# Power.net
KiCad netlist of a schematic drawn in Altium Designer
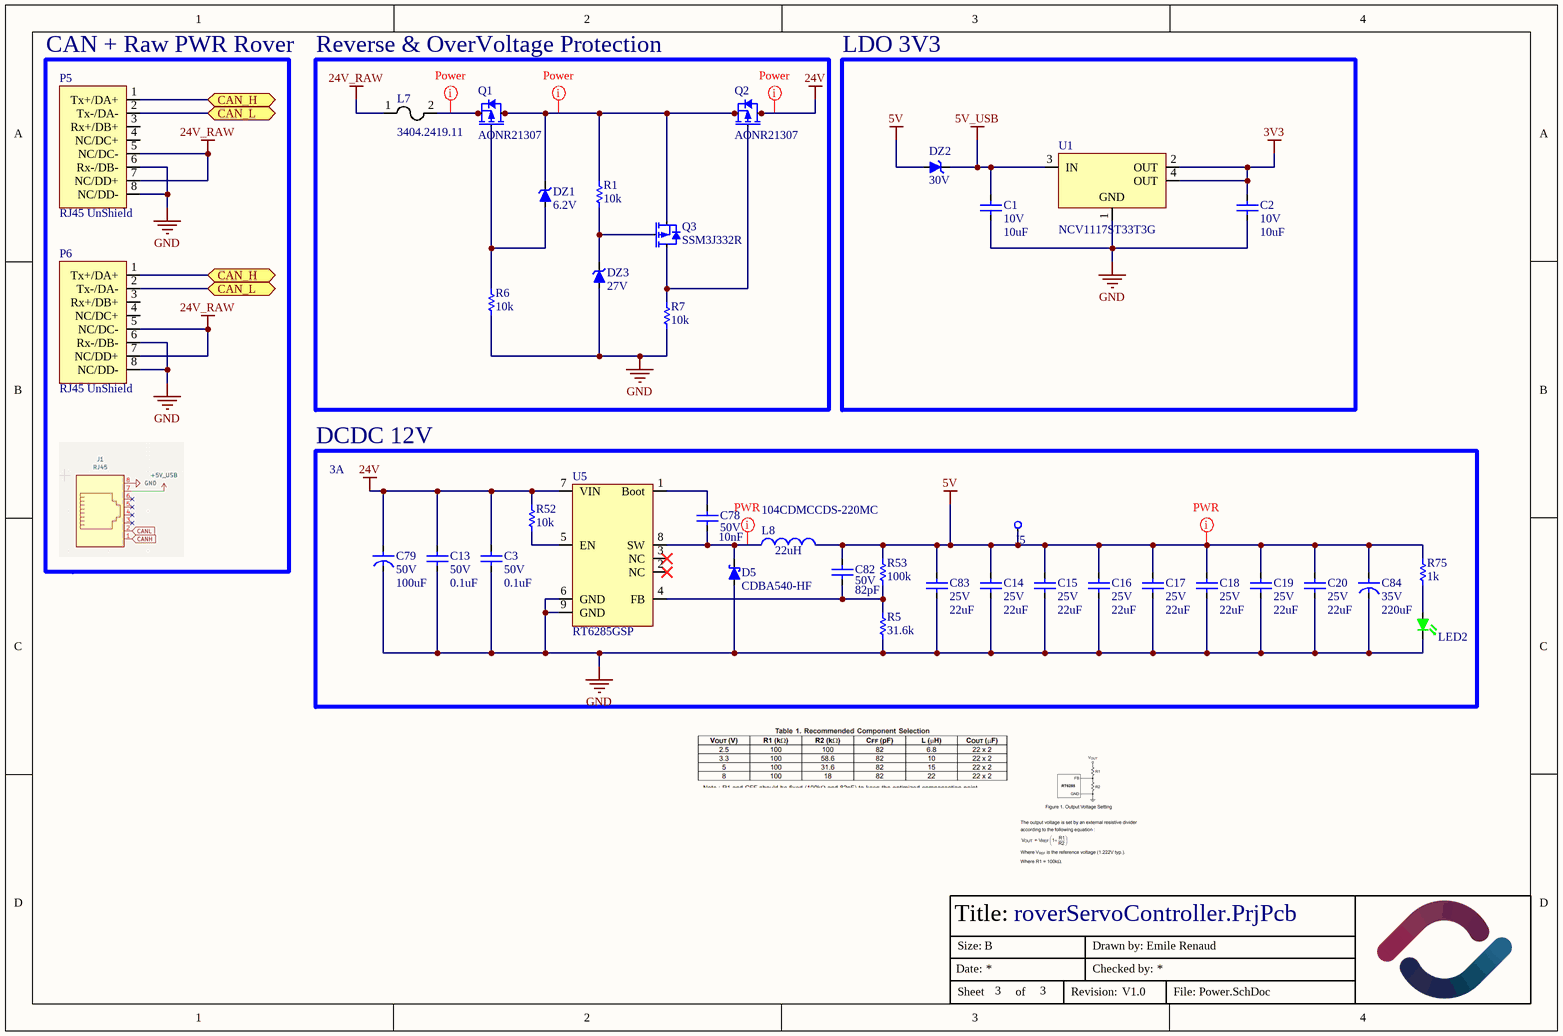
[diagram p0: Power.SchDoc]

(export (version "E")
  (design (tool "Eeschema 10.0.6"))
  (components
    (comp (ref "C1")
      (value "10uF")
      (footprint "CAPACITOR-0603")
      (description "10 µF ±20% 10V Ceramic Capacitor X5R 0603 (1608 Metric)")
      (fields (field (name "VOLT") "10V") (field (name "Comment") "Capacitor-0603-10uF-10V-X5R"))
      (libsource (lib "Capacitors") (part "Capacitor-0603-10uF-10V-X5R"))
    )
    (comp (ref "C2")
      (value "10uF")
      (footprint "CAPACITOR-0603")
      (description "10 µF ±20% 10V Ceramic Capacitor X5R 0603 (1608 Metric)")
      (fields (field (name "VOLT") "10V") (field (name "Comment") "Capacitor-0603-10uF-10V-X5R"))
      (libsource (lib "Capacitors") (part "Capacitor-0603-10uF-10V-X5R"))
    )
    (comp (ref "C3")
      (value "0.1uF")
      (footprint "CAPACITOR-0603")
      (description "Capacitor-0603-0.1uF-50V-X7R")
      (fields (field (name "VOLT") "50V"))
      (libsource (lib "Capacitors") (part "Capacitor-0603-0.1uF-50V-X7R"))
    )
    (comp (ref "C13")
      (value "0.1uF")
      (footprint "CAPACITOR-0603")
      (description "Capacitor-0603-0.1uF-50V-X7R")
      (fields (field (name "VOLT") "50V"))
      (libsource (lib "Capacitors") (part "Capacitor-0603-0.1uF-50V-X7R"))
    )
    (comp (ref "C14")
      (value "22uF")
      (footprint "CAPACITOR-0805")
      (description "Capacitor-0805-22uF-25V-X5R")
      (fields (field (name "VOLT") "25V"))
      (libsource (lib "Capacitors") (part "Capacitor-0805-22uF-25V-X5R"))
    )
    (comp (ref "C15")
      (value "22uF")
      (footprint "CAPACITOR-0805")
      (description "Capacitor-0805-22uF-25V-X5R")
      (fields (field (name "VOLT") "25V"))
      (libsource (lib "Capacitors") (part "Capacitor-0805-22uF-25V-X5R"))
    )
    (comp (ref "C16")
      (value "22uF")
      (footprint "CAPACITOR-0805")
      (description "Capacitor-0805-22uF-25V-X5R")
      (fields (field (name "VOLT") "25V"))
      (libsource (lib "Capacitors") (part "Capacitor-0805-22uF-25V-X5R"))
    )
    (comp (ref "C17")
      (value "22uF")
      (footprint "CAPACITOR-0805")
      (description "Capacitor-0805-22uF-25V-X5R")
      (fields (field (name "VOLT") "25V"))
      (libsource (lib "Capacitors") (part "Capacitor-0805-22uF-25V-X5R"))
    )
    (comp (ref "C18")
      (value "22uF")
      (footprint "CAPACITOR-0805")
      (description "Capacitor-0805-22uF-25V-X5R")
      (fields (field (name "VOLT") "25V"))
      (libsource (lib "Capacitors") (part "Capacitor-0805-22uF-25V-X5R"))
    )
    (comp (ref "C19")
      (value "22uF")
      (footprint "CAPACITOR-0805")
      (description "Capacitor-0805-22uF-25V-X5R")
      (fields (field (name "VOLT") "25V"))
      (libsource (lib "Capacitors") (part "Capacitor-0805-22uF-25V-X5R"))
    )
    (comp (ref "C20")
      (value "22uF")
      (footprint "CAPACITOR-0805")
      (description "Capacitor-0805-22uF-25V-X5R")
      (fields (field (name "VOLT") "25V"))
      (libsource (lib "Capacitors") (part "Capacitor-0805-22uF-25V-X5R"))
    )
    (comp (ref "C78")
      (value "10nF")
      (footprint "CAPACITOR-0603")
      (description "Capacitor-0603-10nF-50V-X7R")
      (fields (field (name "VOLT") "50V"))
      (libsource (lib "Capacitors") (part "Capacitor-0603-10nF-50V-X7R"))
    )
    (comp (ref "C79")
      (value "100uF")
      (footprint "CAP_J-V_8X10P5_RUB")
      (description "CAP ALUM 100UF 20% 50V SMD")
      (fields (field (name "VOLT") "50V") (field (name "Comment") "CAP ALUM 100UF 20% 25V SMD"))
      (libsource (lib "Capacitors-Electrolytic") (part "Capacitor-100uF-50V-SMD"))
    )
    (comp (ref "C82")
      (value "82pF")
      (footprint "CAPACITOR-0603")
      (description "Capacitor-0603-82pF-50V-C0G")
      (fields (field (name "VOLT") "50V"))
      (libsource (lib "Capacitors") (part "Capacitor-0603-82pF-50V-C0G"))
    )
    (comp (ref "C83")
      (value "22uF")
      (footprint "CAPACITOR-0805")
      (description "Capacitor-0805-22uF-25V-X5R")
      (fields (field (name "VOLT") "25V"))
      (libsource (lib "Capacitors") (part "Capacitor-0805-22uF-25V-X5R"))
    )
    (comp (ref "C84")
      (value "220uF")
      (footprint "CAP_J-V_8X10P5_RUB")
      (description "CAP ALUM 220UF 20% 35V SMD")
      (fields (field (name "VOLT") "35V"))
      (libsource (lib "Capacitors-Electrolytic") (part "Capacitor-220uF-35V-SMD"))
    )
    (comp (ref "D5")
      (value "CDBA540-HF")
      (footprint "SMA/DO-214AC")
      (description "DIODE SCHOTTKY 40V 5A SMA")
      (libsource (lib "diodes") (part "CDBA540-HF"))
    )
    (comp (ref "DZ1")
      (value "BZT52C6V2-TP")
      (footprint "SOD-123")
      (description "Zener Diode 6.2 V 200 mW ±6% Surface Mount SOD-123")
      (fields (field (name "VOLT") "6.2V"))
      (libsource (lib "diodes-zener") (part "BZT52C6V2-TP"))
    )
    (comp (ref "DZ2")
      (value "MSS1P3L-M3/89A")
      (footprint "DO-219AD")
      (description "Diode 30 V 1A Surface Mount MicroSMP (DO-219AD)")
      (fields (field (name "VOLT") "30V"))
      (libsource (lib "diodes-zener") (part "MSS1P3L-M3/89A"))
    )
    (comp (ref "DZ3")
      (value "MMSZ5254B-TP")
      (footprint "SOD-123F")
      (description "DIODE ZENER 27V 500MW SOD123")
      (fields (field (name "VOLT") "27V"))
      (libsource (lib "diodes-zener") (part "MMSZ5254B-TP"))
    )
    (comp (ref "J5")
      (value "hole")
      (footprint "HOLE-0.53MM")
      (description "Hole for 28 AWG Solid Wire")
      (libsource (lib "JumpersAndHoles") (part "Hole 0.53mm AWG28-Solid"))
    )
    (comp (ref "L7")
      (value "3404.2419.11")
      (footprint "2-SMD-Fuse")
      (libsource (lib "Fuses") (part "3404.2419.11"))
    )
    (comp (ref "L8")
      (value "104CDMCCDS-220MC")
      (footprint "Inductor_22UH 5A")
      (description "FIXED IND 22UH 5A 66 MOHM SMD")
      (fields (field (name "ALTIUM_VALUE") "22uH"))
      (libsource (lib "Inductors") (part "104CDMCCDS-220MC"))
    )
    (comp (ref "LED2")
      (value "3147-B1911NG--20D000214U1930CT-ND")
      (footprint "LED-0603-2PIN-SILKSCREEN")
      (description "LED GREEN DIFFUSED 0603 SMD")
      (libsource (lib "LEDs") (part "LED_GREEN"))
    )
    (comp (ref "P5")
      (value "RJ45 UnShield")
      (footprint "AMPHENOL_54602-908LF")
      (description "Jack Modular Connector 8p8c (RJ45, Ethernet) 90° Angle (Right) Unshielded Cat3")
      (libsource (lib "PC-connector") (part "RJ545"))
    )
    (comp (ref "P6")
      (value "RJ45 UnShield")
      (footprint "AMPHENOL_54602-908LF")
      (description "Jack Modular Connector 8p8c (RJ45, Ethernet) 90° Angle (Right) Unshielded Cat3")
      (libsource (lib "PC-connector") (part "RJ545"))
    )
    (comp (ref "Q1")
      (value "AONR21307")
      (footprint "DFN8_3x3_Power")
      (description "MOSFET P-CH 30V 24A 8DFN")
      (libsource (lib "FET-P-Small") (part "AONR21307"))
    )
    (comp (ref "Q2")
      (value "AONR21307")
      (footprint "DFN8_3x3_Power")
      (description "MOSFET P-CH 30V 24A 8DFN")
      (libsource (lib "FET-P-Small") (part "AONR21307"))
    )
    (comp (ref "Q3")
      (value "SSM3J332R")
      (footprint "SOT-23-3")
      (description "P-Channel 30 V 6A (Ta) 1W (Ta) Surface Mount SOT-23F")
      (libsource (lib "FET-P-Small") (part "SSM3J332R"))
    )
    (comp (ref "R1")
      (value "10k")
      (footprint "Resistor-0603")
      (description "Resistor0603-10k")
      (fields (field (name "Comment") "SMT resistor"))
      (libsource (lib "Resistors") (part "Resistor0603-10k"))
    )
    (comp (ref "R5")
      (value "31.6k")
      (footprint "Resistor-0603")
      (description "Resistor0603-31.6k")
      (fields (field (name "Comment") "SMT resistor"))
      (libsource (lib "Resistors") (part "Resistor-0603-31.6k"))
    )
    (comp (ref "R6")
      (value "10k")
      (footprint "Resistor-0603")
      (description "Resistor0603-10k")
      (fields (field (name "Comment") "SMT resistor"))
      (libsource (lib "Resistors") (part "Resistor0603-10k"))
    )
    (comp (ref "R7")
      (value "10k")
      (footprint "Resistor-0603")
      (description "Resistor0603-10k")
      (fields (field (name "Comment") "SMT resistor"))
      (libsource (lib "Resistors") (part "Resistor0603-10k"))
    )
    (comp (ref "R52")
      (value "10k")
      (footprint "Resistor-0603")
      (description "Resistor0603-10k")
      (fields (field (name "Comment") "SMT resistor"))
      (libsource (lib "Resistors") (part "Resistor-0603-10k"))
    )
    (comp (ref "R53")
      (value "100k")
      (footprint "Resistor-0603")
      (description "Resistor0603-100k")
      (fields (field (name "Comment") "SMT resistor"))
      (libsource (lib "Resistors") (part "Resistor-0603-100k"))
    )
    (comp (ref "R75")
      (value "1k")
      (footprint "Resistor-0603")
      (description "Resistor0603-1k")
      (fields (field (name "Comment") "SMT resistor"))
      (libsource (lib "Resistors") (part "Resistor-0603-1k"))
    )
    (comp (ref "U1")
      (value "NCV1117ST33T3G")
      (footprint "SOT-223-3/TO-261-3S")
      (description "IC REG LINEAR 3.3V 1A SOT223")
      (libsource (lib "PMIC-VoltageRegulators-LinearRegulators") (part "NCV1117ST33T3G"))
    )
    (comp (ref "U5")
      (value "RT6285GSP")
      (footprint "SOIC-8-EXPOSED-PAD")
      (fields (field (name "HELPURL") "file:///C:/Users/Emile/Downloads/DS6285-00.pdf"))
      (libsource (lib "PMIC-VoltageRegulators-DCDCSwitchingRegulators") (part "RT6285GSP"))
    )
  )
  (nets
    (net (code "1") (name "/CAN_H") (class "Default")
      (node (ref "P5") (pin "1") (pinfunction "Tx+/DA+_1") (pintype "passive"))
      (node (ref "P6") (pin "1") (pinfunction "Tx+/DA+_1") (pintype "passive"))
    )
    (net (code "2") (name "/CAN_L") (class "Default")
      (node (ref "P5") (pin "2") (pinfunction "Tx-/DA-_2") (pintype "passive"))
      (node (ref "P6") (pin "2") (pinfunction "Tx-/DA-_2") (pintype "passive"))
    )
    (net (code "3") (name "3V3") (class "Default")
      (node (ref "C2") (pin "2") (pinfunction "2_2") (pintype "passive"))
      (node (ref "U1") (pin "2") (pinfunction "OUT_2") (pintype "passive"))
      (node (ref "U1") (pin "4") (pinfunction "OUT_4") (pintype "passive"))
    )
    (net (code "4") (name "5V") (class "Default")
      (node (ref "C14") (pin "2") (pinfunction "2_2") (pintype "passive"))
      (node (ref "C15") (pin "2") (pinfunction "2_2") (pintype "passive"))
      (node (ref "C16") (pin "2") (pinfunction "2_2") (pintype "passive"))
      (node (ref "C17") (pin "2") (pinfunction "2_2") (pintype "passive"))
      (node (ref "C18") (pin "2") (pinfunction "2_2") (pintype "passive"))
      (node (ref "C19") (pin "2") (pinfunction "2_2") (pintype "passive"))
      (node (ref "C20") (pin "2") (pinfunction "2_2") (pintype "passive"))
      (node (ref "C82") (pin "2") (pinfunction "2_2") (pintype "passive"))
      (node (ref "C83") (pin "2") (pinfunction "2_2") (pintype "passive"))
      (node (ref "C84") (pin "1") (pinfunction "1_1") (pintype "passive"))
      (node (ref "DZ2") (pin "2") (pinfunction "A_2") (pintype "passive"))
      (node (ref "J5") (pin "1") (pinfunction "1_1") (pintype "passive"))
      (node (ref "L8") (pin "2") (pinfunction "2_2") (pintype "passive"))
      (node (ref "R53") (pin "2") (pinfunction "2_2") (pintype "passive"))
      (node (ref "R75") (pin "2") (pinfunction "2_2") (pintype "passive"))
    )
    (net (code "5") (name "5V_USB") (class "Default")
      (node (ref "C1") (pin "2") (pinfunction "2_2") (pintype "passive"))
      (node (ref "DZ2") (pin "1") (pinfunction "K_1") (pintype "passive"))
      (node (ref "U1") (pin "3") (pinfunction "IN_3") (pintype "passive"))
    )
    (net (code "6") (name "24V") (class "Default")
      (node (ref "C13") (pin "2") (pinfunction "2_2") (pintype "passive"))
      (node (ref "C3") (pin "2") (pinfunction "2_2") (pintype "passive"))
      (node (ref "C79") (pin "1") (pinfunction "1_1") (pintype "passive"))
      (node (ref "Q2") (pin "5") (pinfunction "D_5") (pintype "passive"))
      (node (ref "Q2") (pin "6") (pinfunction "D_6") (pintype "passive"))
      (node (ref "Q2") (pin "7") (pinfunction "D_7") (pintype "passive"))
      (node (ref "Q2") (pin "8") (pinfunction "D_8") (pintype "passive"))
      (node (ref "R52") (pin "2") (pinfunction "2_2") (pintype "passive"))
      (node (ref "U5") (pin "7") (pinfunction "VIN_7") (pintype "passive"))
    )
    (net (code "7") (name "24V_RAW") (class "Default")
      (node (ref "L7") (pin "1") (pinfunction "1_1") (pintype "passive"))
      (node (ref "P5") (pin "5") (pinfunction "NC/DC-_5") (pintype "passive"))
      (node (ref "P5") (pin "7") (pinfunction "NC/DD+_7") (pintype "passive"))
      (node (ref "P6") (pin "5") (pinfunction "NC/DC-_5") (pintype "passive"))
      (node (ref "P6") (pin "7") (pinfunction "NC/DD+_7") (pintype "passive"))
    )
    (net (code "8") (name "GND") (class "Default")
      (node (ref "C1") (pin "1") (pinfunction "1_1") (pintype "passive"))
      (node (ref "C13") (pin "1") (pinfunction "1_1") (pintype "passive"))
      (node (ref "C14") (pin "1") (pinfunction "1_1") (pintype "passive"))
      (node (ref "C15") (pin "1") (pinfunction "1_1") (pintype "passive"))
      (node (ref "C16") (pin "1") (pinfunction "1_1") (pintype "passive"))
      (node (ref "C17") (pin "1") (pinfunction "1_1") (pintype "passive"))
      (node (ref "C18") (pin "1") (pinfunction "1_1") (pintype "passive"))
      (node (ref "C19") (pin "1") (pinfunction "1_1") (pintype "passive"))
      (node (ref "C2") (pin "1") (pinfunction "1_1") (pintype "passive"))
      (node (ref "C20") (pin "1") (pinfunction "1_1") (pintype "passive"))
      (node (ref "C3") (pin "1") (pinfunction "1_1") (pintype "passive"))
      (node (ref "C79") (pin "2") (pinfunction "2_2") (pintype "passive"))
      (node (ref "C83") (pin "1") (pinfunction "1_1") (pintype "passive"))
      (node (ref "C84") (pin "2") (pinfunction "2_2") (pintype "passive"))
      (node (ref "D5") (pin "1") (pinfunction "A_1") (pintype "passive"))
      (node (ref "DZ3") (pin "1") (pinfunction "A_1") (pintype "passive"))
      (node (ref "LED2") (pin "1") (pinfunction "K_1") (pintype "passive"))
      (node (ref "P5") (pin "6") (pinfunction "Rx-/DB-_6") (pintype "passive"))
      (node (ref "P5") (pin "8") (pinfunction "NC/DD-_8") (pintype "passive"))
      (node (ref "P6") (pin "6") (pinfunction "Rx-/DB-_6") (pintype "passive"))
      (node (ref "P6") (pin "8") (pinfunction "NC/DD-_8") (pintype "passive"))
      (node (ref "R5") (pin "1") (pinfunction "1_1") (pintype "passive"))
      (node (ref "R6") (pin "1") (pinfunction "1_1") (pintype "passive"))
      (node (ref "R7") (pin "1") (pinfunction "1_1") (pintype "passive"))
      (node (ref "U1") (pin "1") (pinfunction "GND_1") (pintype "passive"))
      (node (ref "U5") (pin "6") (pinfunction "GND_6") (pintype "passive"))
      (node (ref "U5") (pin "9") (pinfunction "GND_9") (pintype "passive"))
    )
    (net (code "9") (name "Net-(D5-K)") (class "Default")
      (node (ref "C78") (pin "1") (pinfunction "1_1") (pintype "passive"))
      (node (ref "D5") (pin "2") (pinfunction "K_2") (pintype "passive"))
      (node (ref "L8") (pin "1") (pinfunction "1_1") (pintype "passive"))
      (node (ref "U5") (pin "8") (pinfunction "SW_8") (pintype "passive"))
    )
    (net (code "10") (name "Net-(DZ1-A)") (class "Default")
      (node (ref "DZ1") (pin "1") (pinfunction "A_1") (pintype "passive"))
      (node (ref "Q1") (pin "4") (pinfunction "G_4") (pintype "passive"))
      (node (ref "R6") (pin "2") (pinfunction "2_2") (pintype "passive"))
    )
    (net (code "11") (name "Net-(DZ1-K)") (class "Default")
      (node (ref "DZ1") (pin "2") (pinfunction "K_2") (pintype "passive"))
      (node (ref "Q1") (pin "5") (pinfunction "D_5") (pintype "passive"))
      (node (ref "Q1") (pin "6") (pinfunction "D_6") (pintype "passive"))
      (node (ref "Q1") (pin "7") (pinfunction "D_7") (pintype "passive"))
      (node (ref "Q1") (pin "8") (pinfunction "D_8") (pintype "passive"))
      (node (ref "Q2") (pin "1") (pinfunction "S_1") (pintype "passive"))
      (node (ref "Q2") (pin "2") (pinfunction "S_2") (pintype "passive"))
      (node (ref "Q2") (pin "3") (pinfunction "S_3") (pintype "passive"))
      (node (ref "Q3") (pin "2") (pinfunction "S_2") (pintype "passive"))
      (node (ref "R1") (pin "2") (pinfunction "2_2") (pintype "passive"))
    )
    (net (code "12") (name "Net-(DZ3-K)") (class "Default")
      (node (ref "DZ3") (pin "2") (pinfunction "K_2") (pintype "passive"))
      (node (ref "Q3") (pin "1") (pinfunction "G_1") (pintype "passive"))
      (node (ref "R1") (pin "1") (pinfunction "1_1") (pintype "passive"))
    )
    (net (code "13") (name "Net-(L7-Pad2)") (class "Default")
      (node (ref "L7") (pin "2") (pinfunction "2_2") (pintype "passive"))
      (node (ref "Q1") (pin "1") (pinfunction "S_1") (pintype "passive"))
      (node (ref "Q1") (pin "2") (pinfunction "S_2") (pintype "passive"))
      (node (ref "Q1") (pin "3") (pinfunction "S_3") (pintype "passive"))
    )
    (net (code "14") (name "Net-(LED2-R)") (class "Default")
      (node (ref "LED2") (pin "2") (pinfunction "R_2") (pintype "passive"))
      (node (ref "R75") (pin "1") (pinfunction "1_1") (pintype "passive"))
    )
    (net (code "15") (name "Net-(Q2-G)") (class "Default")
      (node (ref "Q2") (pin "4") (pinfunction "G_4") (pintype "passive"))
      (node (ref "Q3") (pin "3") (pinfunction "D_3") (pintype "passive"))
      (node (ref "R7") (pin "2") (pinfunction "2_2") (pintype "passive"))
    )
    (net (code "16") (name "Net-(U5-Boot)") (class "Default")
      (node (ref "C78") (pin "2") (pinfunction "2_2") (pintype "passive"))
      (node (ref "U5") (pin "1") (pinfunction "Boot_1") (pintype "passive"))
    )
    (net (code "17") (name "Net-(U5-EN)") (class "Default")
      (node (ref "R52") (pin "1") (pinfunction "1_1") (pintype "passive"))
      (node (ref "U5") (pin "5") (pinfunction "EN_5") (pintype "passive"))
    )
    (net (code "18") (name "Net-(U5-FB)") (class "Default")
      (node (ref "C82") (pin "1") (pinfunction "1_1") (pintype "passive"))
      (node (ref "R5") (pin "2") (pinfunction "2_2") (pintype "passive"))
      (node (ref "R53") (pin "1") (pinfunction "1_1") (pintype "passive"))
      (node (ref "U5") (pin "4") (pinfunction "FB_4") (pintype "passive"))
    )
    (net (code "19") (name "unconnected-(P5-NC{slash}DC+-Pad4)") (class "Default")
      (node (ref "P5") (pin "4") (pinfunction "NC/DC+_4") (pintype "passive"))
    )
    (net (code "20") (name "unconnected-(P5-Rx+{slash}DB+-Pad3)") (class "Default")
      (node (ref "P5") (pin "3") (pinfunction "Rx+/DB+_3") (pintype "passive"))
    )
    (net (code "21") (name "unconnected-(P6-NC{slash}DC+-Pad4)") (class "Default")
      (node (ref "P6") (pin "4") (pinfunction "NC/DC+_4") (pintype "passive"))
    )
    (net (code "22") (name "unconnected-(P6-Rx+{slash}DB+-Pad3)") (class "Default")
      (node (ref "P6") (pin "3") (pinfunction "Rx+/DB+_3") (pintype "passive"))
    )
    (net (code "23") (name "unconnected-(U5-NC-Pad2)") (class "Default")
      (node (ref "U5") (pin "2") (pinfunction "NC_2") (pintype "passive+no_connect"))
    )
    (net (code "24") (name "unconnected-(U5-NC-Pad3)") (class "Default")
      (node (ref "U5") (pin "3") (pinfunction "NC_3") (pintype "passive+no_connect"))
    )
  )
)
